# BackscatterPlantSensor_v2_test.net
KiCad netlist of a schematic drawn in EAGLE
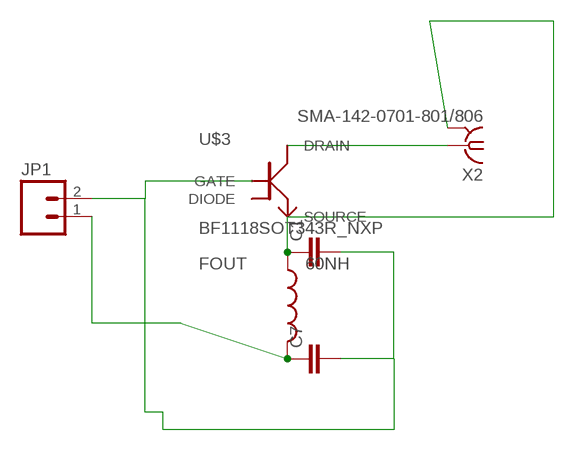
[diagram p0: schematic, sheet 1]

(export (version "E")
  (design (tool "Eeschema 10.0.6"))
  (components
    (comp (ref "60NH")
      (value "INDUCTOR0402")
      (footprint "eagle-import:C0402")
      (libsource (lib "eagle-import") (part "INDUCTOR0402"))
    )
    (comp (ref "C1")
      (value "CAP0402-CAP")
      (footprint "eagle-import:0402-CAP")
      (libsource (lib "eagle-import") (part "CAP0402-CAP"))
    )
    (comp (ref "C7")
      (value "CAP0402-CAP")
      (footprint "eagle-import:0402-CAP")
      (libsource (lib "eagle-import") (part "CAP0402-CAP"))
    )
    (comp (ref "JP1")
      (value "M02PTH")
      (footprint "eagle-import:1X02")
      (libsource (lib "eagle-import") (part "M02PTH"))
    )
    (comp (ref "U$3")
      (value "BF1118SOT343R_NXP")
      (footprint "eagle-import:SOT343R")
      (libsource (lib "eagle-import") (part "BF1118SOT343R_NXP"))
    )
    (comp (ref "X2")
      (value "SMA-142-0701-801/806")
      (footprint "eagle-import:J502-ND-142-0701-801_806")
      (fields (field (name "MF") "JOHNSON COMPONENTS") (field (name "MPN") "142-0701-801"))
      (libsource (lib "eagle-import") (part "SMA-142-0701-801/806"))
    )
  )
  (nets
    (net (code "1") (name "FOUT") (class "Default")
      (node (ref "60NH") (pin "2") (pinfunction "2_2") (pintype "passive"))
      (node (ref "C7") (pin "1") (pinfunction "1_1") (pintype "passive"))
      (node (ref "JP1") (pin "1") (pinfunction "1_1") (pintype "passive"))
    )
    (net (code "2") (name "Net-(U$3-DRAIN)") (class "Default")
      (node (ref "U$3") (pin "4") (pinfunction "DRAIN_4") (pintype "bidirectional"))
      (node (ref "X2") (pin "1") (pinfunction "1_1") (pintype "passive"))
    )
    (net (code "3") (name "Net-(U$3-GATE)") (class "Default")
      (node (ref "C1") (pin "2") (pinfunction "2_2") (pintype "passive"))
      (node (ref "C7") (pin "2") (pinfunction "2_2") (pintype "passive"))
      (node (ref "JP1") (pin "2") (pinfunction "2_2") (pintype "passive"))
      (node (ref "U$3") (pin "1") (pinfunction "GATE_1") (pintype "bidirectional"))
    )
    (net (code "4") (name "Net-(U$3-SOURCE)") (class "Default")
      (node (ref "60NH") (pin "1") (pinfunction "1_1") (pintype "passive"))
      (node (ref "C1") (pin "1") (pinfunction "1_1") (pintype "passive"))
      (node (ref "U$3") (pin "3") (pinfunction "SOURCE_3") (pintype "bidirectional"))
      (node (ref "X2") (pin "G@1") (pinfunction "GND_G@1") (pintype "power_in"))
    )
    (net (code "5") (name "unconnected-(U$3-DIODE-Pad2)") (class "Default")
      (node (ref "U$3") (pin "2") (pinfunction "DIODE_2") (pintype "bidirectional"))
    )
  )
)
